# DDR3.net
KiCad netlist of a schematic drawn in Altium Designer
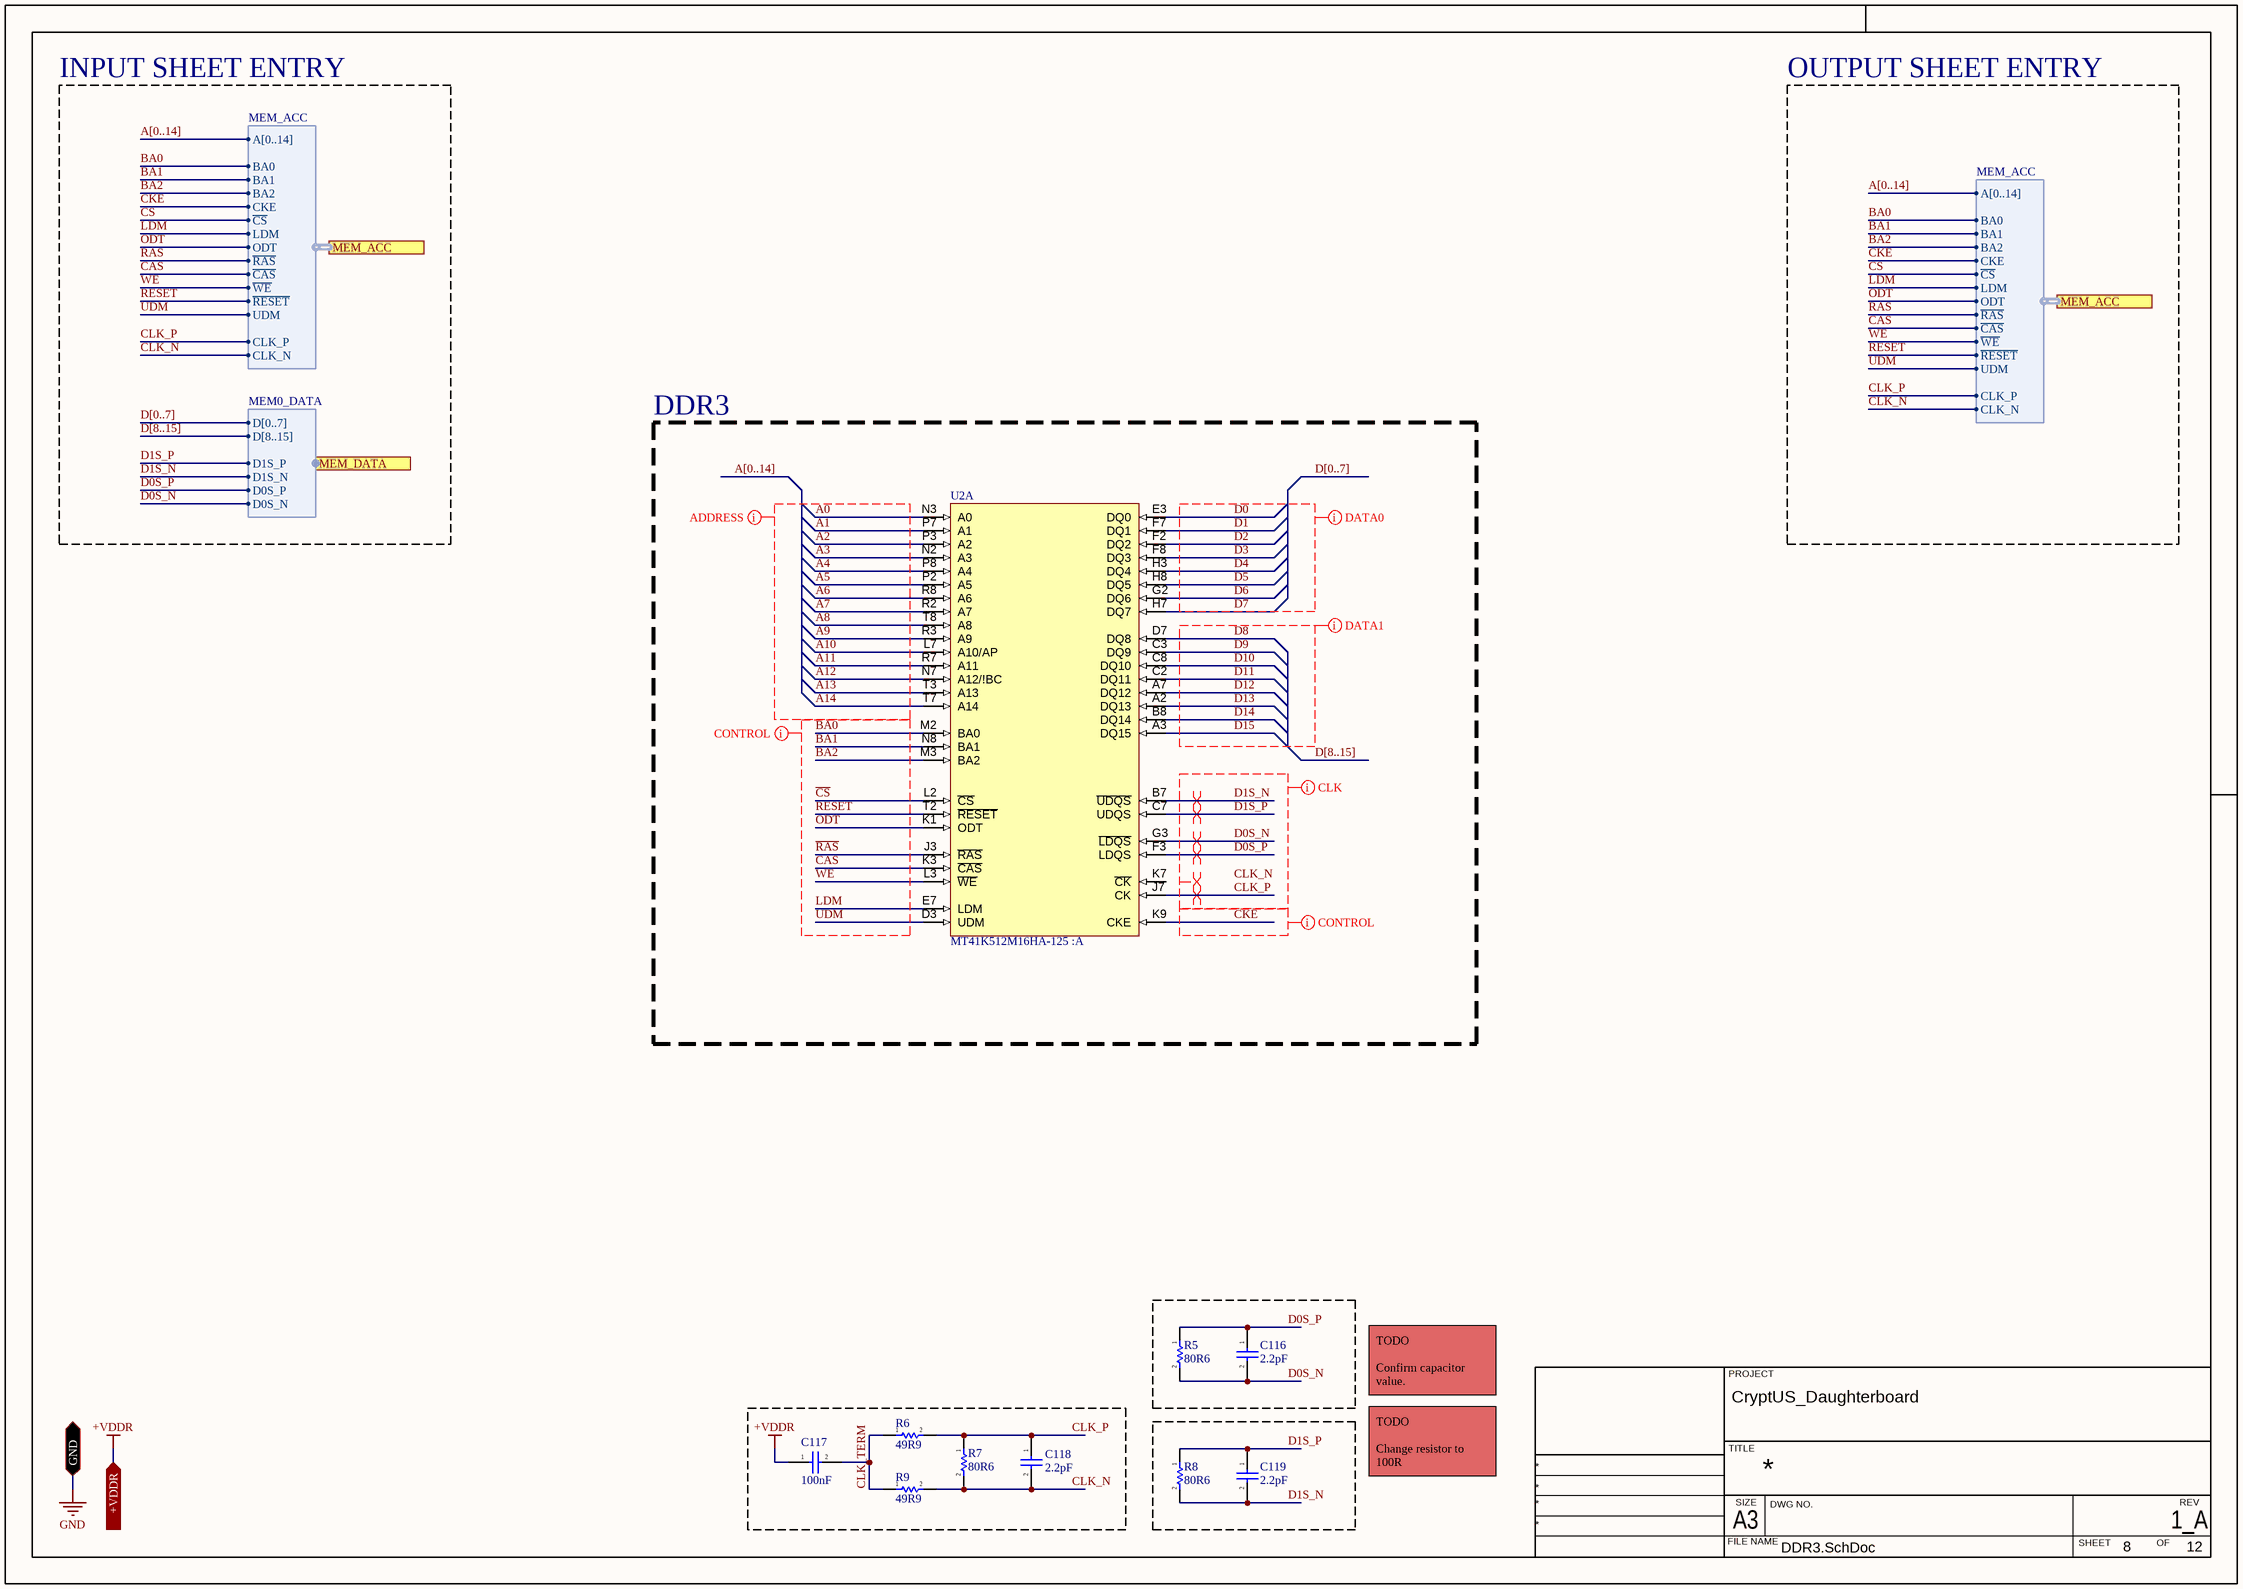
[diagram p0: DDR3.SchDoc]

(export (version "E")
  (design (tool "Eeschema 10.0.6"))
  (components
    (comp (ref "C116")
      (value "2.2pF")
      (footprint "CAP_0402")
      (description "Generic SMT Ceramic Capacitor")
      (libsource (lib "Symbols") (part "CAP_CER"))
    )
    (comp (ref "C117")
      (value "100nF")
      (footprint "CAP_0402")
      (description "Generic SMT Ceramic Capacitor")
      (libsource (lib "Symbols") (part "CAP_CER"))
    )
    (comp (ref "C118")
      (value "2.2pF")
      (footprint "CAP_0402")
      (description "Generic SMT Ceramic Capacitor")
      (libsource (lib "Symbols") (part "CAP_CER"))
    )
    (comp (ref "C119")
      (value "2.2pF")
      (footprint "CAP_0402")
      (description "Generic SMT Ceramic Capacitor")
      (libsource (lib "Symbols") (part "CAP_CER"))
    )
    (comp (ref "R5")
      (value "80R6")
      (footprint "RES_0402")
      (description "Resistor")
      (fields (field (name "POWER") "1/8W") (field (name "TOLERANCE") "0.5%"))
      (libsource (lib "Symbols") (part "RESISTOR"))
    )
    (comp (ref "R6")
      (value "49R9")
      (footprint "RES_0402")
      (description "Resistor")
      (fields (field (name "POWER") "1/8W") (field (name "TOLERANCE") "0.5%"))
      (libsource (lib "Symbols") (part "RESISTOR"))
    )
    (comp (ref "R7")
      (value "80R6")
      (footprint "RES_0402")
      (description "Resistor")
      (fields (field (name "POWER") "1/8W") (field (name "TOLERANCE") "0.5%"))
      (libsource (lib "Symbols") (part "RESISTOR"))
    )
    (comp (ref "R8")
      (value "80R6")
      (footprint "RES_0402")
      (description "Resistor")
      (fields (field (name "POWER") "1/8W") (field (name "TOLERANCE") "0.5%"))
      (libsource (lib "Symbols") (part "RESISTOR"))
    )
    (comp (ref "R9")
      (value "49R9")
      (footprint "RES_0402")
      (description "Resistor")
      (fields (field (name "POWER") "1/8W") (field (name "TOLERANCE") "0.5%"))
      (libsource (lib "Symbols") (part "RESISTOR"))
    )
    (comp (ref "U2")
      (value "MT41K512M16HA-125 :A")
      (footprint "FBGA-96")
      (description "DRAM 8G 1.35V 512Mx16 800 MHz DDR3 0C-90C")
      (fields (field (name "MFR") "Alliance Memory"))
      (libsource (lib "CryptLib") (part "IC_MT41K512M16HA-125"))
    )
  )
  (nets
    (net (code "3") (name "+VDDR") (class "Default")
      (node (ref "C117") (pin "1") (pinfunction "1_1") (pintype "passive"))
    )
    (net (code "4") (name "/A0") (class "Default")
      (node (ref "U2") (pin "N3") (pinfunction "A0_N3") (pintype "input"))
    )
    (net (code "5") (name "/A1") (class "Default")
      (node (ref "U2") (pin "P7") (pinfunction "A1_P7") (pintype "input"))
    )
    (net (code "6") (name "/A2") (class "Default")
      (node (ref "U2") (pin "P3") (pinfunction "A2_P3") (pintype "input"))
    )
    (net (code "7") (name "/A3") (class "Default")
      (node (ref "U2") (pin "N2") (pinfunction "A3_N2") (pintype "input"))
    )
    (net (code "8") (name "/A4") (class "Default")
      (node (ref "U2") (pin "P8") (pinfunction "A4_P8") (pintype "input"))
    )
    (net (code "9") (name "/A5") (class "Default")
      (node (ref "U2") (pin "P2") (pinfunction "A5_P2") (pintype "input"))
    )
    (net (code "10") (name "/A6") (class "Default")
      (node (ref "U2") (pin "R8") (pinfunction "A6_R8") (pintype "input"))
    )
    (net (code "11") (name "/A7") (class "Default")
      (node (ref "U2") (pin "R2") (pinfunction "A7_R2") (pintype "input"))
    )
    (net (code "12") (name "/A8") (class "Default")
      (node (ref "U2") (pin "T8") (pinfunction "A8_T8") (pintype "input"))
    )
    (net (code "13") (name "/A9") (class "Default")
      (node (ref "U2") (pin "R3") (pinfunction "A9_R3") (pintype "input"))
    )
    (net (code "14") (name "/A10") (class "Default")
      (node (ref "U2") (pin "L7") (pinfunction "A10/AP_L7") (pintype "input"))
    )
    (net (code "15") (name "/A11") (class "Default")
      (node (ref "U2") (pin "R7") (pinfunction "A11_R7") (pintype "input"))
    )
    (net (code "16") (name "/A12") (class "Default")
      (node (ref "U2") (pin "N7") (pinfunction "A12/!BC_N7") (pintype "input"))
    )
    (net (code "17") (name "/A13") (class "Default")
      (node (ref "U2") (pin "T3") (pinfunction "A13_T3") (pintype "input"))
    )
    (net (code "18") (name "/A14") (class "Default")
      (node (ref "U2") (pin "T7") (pinfunction "A14_T7") (pintype "input"))
    )
    (net (code "20") (name "/BA0") (class "Default")
      (node (ref "U2") (pin "M2") (pinfunction "BA0_M2") (pintype "input"))
    )
    (net (code "21") (name "/BA1") (class "Default")
      (node (ref "U2") (pin "N8") (pinfunction "BA1_N8") (pintype "input"))
    )
    (net (code "22") (name "/BA2") (class "Default")
      (node (ref "U2") (pin "M3") (pinfunction "BA2_M3") (pintype "input"))
    )
    (net (code "23") (name "/CKE") (class "Default")
      (node (ref "U2") (pin "K9") (pinfunction "CKE_K9") (pintype "input"))
    )
    (net (code "24") (name "/CLK_N") (class "Default")
      (node (ref "C118") (pin "2") (pinfunction "2_2") (pintype "passive"))
      (node (ref "R7") (pin "2") (pinfunction "2_2") (pintype "passive"))
      (node (ref "R9") (pin "2") (pinfunction "2_2") (pintype "passive"))
    )
    (net (code "25") (name "/CLK_P") (class "Default")
      (node (ref "C118") (pin "1") (pinfunction "1_1") (pintype "passive"))
      (node (ref "R6") (pin "2") (pinfunction "2_2") (pintype "passive"))
      (node (ref "R7") (pin "1") (pinfunction "1_1") (pintype "passive"))
      (node (ref "U2") (pin "J7") (pinfunction "CK_J7") (pintype "input"))
    )
    (net (code "26") (name "/CLK_TERM") (class "Default")
      (node (ref "C117") (pin "2") (pinfunction "2_2") (pintype "passive"))
      (node (ref "R6") (pin "1") (pinfunction "1_1") (pintype "passive"))
      (node (ref "R9") (pin "1") (pinfunction "1_1") (pintype "passive"))
    )
    (net (code "27") (name "/D0") (class "Default")
      (node (ref "U2") (pin "E3") (pinfunction "DQ0_E3") (pintype "input"))
    )
    (net (code "28") (name "/D0S_N") (class "Default")
      (node (ref "C116") (pin "2") (pinfunction "2_2") (pintype "passive"))
      (node (ref "R5") (pin "2") (pinfunction "2_2") (pintype "passive"))
      (node (ref "U2") (pin "G3") (pinfunction "~{LDQS}_G3") (pintype "input"))
    )
    (net (code "29") (name "/D0S_P") (class "Default")
      (node (ref "C116") (pin "1") (pinfunction "1_1") (pintype "passive"))
      (node (ref "R5") (pin "1") (pinfunction "1_1") (pintype "passive"))
      (node (ref "U2") (pin "F3") (pinfunction "LDQS_F3") (pintype "input"))
    )
    (net (code "30") (name "/D1") (class "Default")
      (node (ref "U2") (pin "F7") (pinfunction "DQ1_F7") (pintype "input"))
    )
    (net (code "31") (name "/D1S_N") (class "Default")
      (node (ref "C119") (pin "2") (pinfunction "2_2") (pintype "passive"))
      (node (ref "R8") (pin "2") (pinfunction "2_2") (pintype "passive"))
      (node (ref "U2") (pin "B7") (pinfunction "~{UDQS}_B7") (pintype "input"))
    )
    (net (code "32") (name "/D1S_P") (class "Default")
      (node (ref "C119") (pin "1") (pinfunction "1_1") (pintype "passive"))
      (node (ref "R8") (pin "1") (pinfunction "1_1") (pintype "passive"))
      (node (ref "U2") (pin "C7") (pinfunction "UDQS_C7") (pintype "input"))
    )
    (net (code "33") (name "/D2") (class "Default")
      (node (ref "U2") (pin "F2") (pinfunction "DQ2_F2") (pintype "input"))
    )
    (net (code "34") (name "/D3") (class "Default")
      (node (ref "U2") (pin "F8") (pinfunction "DQ3_F8") (pintype "input"))
    )
    (net (code "35") (name "/D4") (class "Default")
      (node (ref "U2") (pin "H3") (pinfunction "DQ4_H3") (pintype "input"))
    )
    (net (code "36") (name "/D5") (class "Default")
      (node (ref "U2") (pin "H8") (pinfunction "DQ5_H8") (pintype "input"))
    )
    (net (code "37") (name "/D6") (class "Default")
      (node (ref "U2") (pin "G2") (pinfunction "DQ6_G2") (pintype "input"))
    )
    (net (code "38") (name "/D7") (class "Default")
      (node (ref "U2") (pin "H7") (pinfunction "DQ7_H7") (pintype "input"))
    )
    (net (code "39") (name "/D8") (class "Default")
      (node (ref "U2") (pin "D7") (pinfunction "DQ8_D7") (pintype "input"))
    )
    (net (code "40") (name "/D9") (class "Default")
      (node (ref "U2") (pin "C3") (pinfunction "DQ9_C3") (pintype "input"))
    )
    (net (code "41") (name "/D10") (class "Default")
      (node (ref "U2") (pin "C8") (pinfunction "DQ10_C8") (pintype "input"))
    )
    (net (code "42") (name "/D11") (class "Default")
      (node (ref "U2") (pin "C2") (pinfunction "DQ11_C2") (pintype "input"))
    )
    (net (code "43") (name "/D12") (class "Default")
      (node (ref "U2") (pin "A7") (pinfunction "DQ12_A7") (pintype "input"))
    )
    (net (code "44") (name "/D13") (class "Default")
      (node (ref "U2") (pin "A2") (pinfunction "DQ13_A2") (pintype "input"))
    )
    (net (code "45") (name "/D14") (class "Default")
      (node (ref "U2") (pin "B8") (pinfunction "DQ14_B8") (pintype "input"))
    )
    (net (code "46") (name "/D15") (class "Default")
      (node (ref "U2") (pin "A3") (pinfunction "DQ15_A3") (pintype "input"))
    )
    (net (code "49") (name "/LDM") (class "Default")
      (node (ref "U2") (pin "E7") (pinfunction "LDM_E7") (pintype "input"))
    )
    (net (code "51") (name "/ODT") (class "Default")
      (node (ref "U2") (pin "K1") (pinfunction "ODT_K1") (pintype "input"))
    )
    (net (code "52") (name "/UDM") (class "Default")
      (node (ref "U2") (pin "D3") (pinfunction "UDM_D3") (pintype "input"))
    )
    (net (code "56") (name "/~{CAS}") (class "Default")
      (node (ref "U2") (pin "K3") (pinfunction "~{CAS}_K3") (pintype "input"))
    )
    (net (code "57") (name "/~{CS}") (class "Default")
      (node (ref "U2") (pin "L2") (pinfunction "~{CS}_L2") (pintype "input"))
    )
    (net (code "58") (name "/~{RAS}") (class "Default")
      (node (ref "U2") (pin "J3") (pinfunction "~{RAS}_J3") (pintype "input"))
    )
    (net (code "59") (name "/~{RESET}") (class "Default")
      (node (ref "U2") (pin "T2") (pinfunction "~{RESET}_T2") (pintype "input"))
    )
    (net (code "60") (name "/~{WE}") (class "Default")
      (node (ref "U2") (pin "L3") (pinfunction "~{WE}_L3") (pintype "input"))
    )
    (net (code "62") (name "unconnected-(U2A-~{CK}-PadK7)") (class "Default")
      (node (ref "U2") (pin "K7") (pinfunction "~{CK}_K7") (pintype "input"))
    )
  )
)
